# MSD.net
KiCad netlist of a schematic drawn in EAGLE
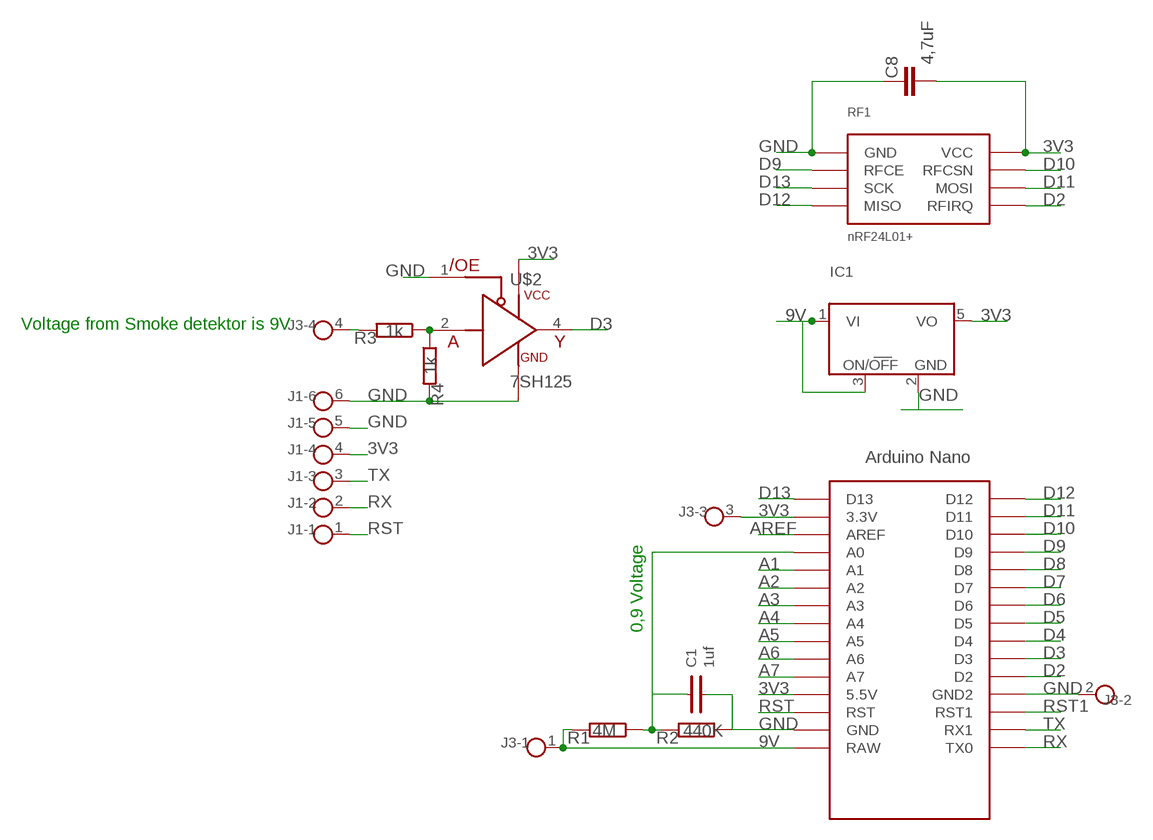
[diagram p0: schematic, sheet 1]

(export (version "E")
  (design (tool "Eeschema 10.0.6"))
  (components
    (comp (ref "C1")
      (value "1uf")
      (footprint "eagle-import:0805")
      (libsource (lib "eagle-import") (part "CC0805"))
    )
    (comp (ref "C8")
      (value "4,7uF")
      (footprint "eagle-import:C1206K")
      (libsource (lib "eagle-import") (part "C-EUC1206K"))
    )
    (comp (ref "IC1")
      (value "LP2980IM5")
      (footprint "eagle-import:SOT23-5")
      (libsource (lib "eagle-import") (part "LP2980IM5"))
    )
    (comp (ref "J1")
      (value "FTDI")
      (footprint "eagle-import:LIST6B")
      (libsource (lib "eagle-import") (part "LIST6LIST6B"))
    )
    (comp (ref "J3")
      (value "LIST4")
      (footprint "eagle-import:LIST4")
      (libsource (lib "eagle-import") (part "LIST4"))
    )
    (comp (ref "R1")
      (value "4M")
      (footprint "eagle-import:R0805")
      (libsource (lib "eagle-import") (part "R-EU_R0805"))
    )
    (comp (ref "R2")
      (value "440K")
      (footprint "eagle-import:R0805")
      (libsource (lib "eagle-import") (part "R-EU_R0805"))
    )
    (comp (ref "R3")
      (value "1k")
      (footprint "eagle-import:R0805")
      (libsource (lib "eagle-import") (part "R-EU_R0805"))
    )
    (comp (ref "R4")
      (value "1k")
      (footprint "eagle-import:R0805")
      (libsource (lib "eagle-import") (part "R-EU_R0805"))
    )
    (comp (ref "RF1")
      (value "nRF24L01+")
      (footprint "eagle-import:2X4-2.54MM")
      (libsource (lib "eagle-import") (part "NRF24L01"))
    )
    (comp (ref "U$1")
      (value "NANO")
      (footprint "eagle-import:NANO")
      (libsource (lib "eagle-import") (part "NANO"))
    )
    (comp (ref "U$2")
      (value "7SH125")
      (footprint "eagle-import:SOT23")
      (libsource (lib "eagle-import") (part "7SH125"))
    )
  )
  (nets
    (net (code "1") (name "/3V3") (class "Default")
      (node (ref "C8") (pin "1") (pinfunction "1_1") (pintype "passive"))
      (node (ref "IC1") (pin "5") (pinfunction "VO_5") (pintype "output"))
      (node (ref "J1") (pin "4") (pinfunction "1_4") (pintype "passive"))
      (node (ref "J3") (pin "3") (pinfunction "1_3") (pintype "passive"))
      (node (ref "RF1") (pin "P$2") (pinfunction "VCC_P$2") (pintype "power_in"))
      (node (ref "U$1") (pin "3.3V") (pinfunction "3.3V_3.3V") (pintype "bidirectional"))
      (node (ref "U$1") (pin "5V") (pinfunction "5.5V_5V") (pintype "bidirectional"))
      (node (ref "U$2") (pin "5") (pinfunction "VCC_5") (pintype "power_in"))
    )
    (net (code "2") (name "/9V") (class "Default")
      (node (ref "IC1") (pin "1") (pinfunction "VI_1") (pintype "input"))
      (node (ref "IC1") (pin "3") (pinfunction "ON/OFF_3") (pintype "input"))
      (node (ref "J3") (pin "1") (pinfunction "1_1") (pintype "passive"))
      (node (ref "R1") (pin "2") (pinfunction "2_2") (pintype "passive"))
      (node (ref "U$1") (pin "RAW") (pinfunction "RAW_RAW") (pintype "bidirectional"))
    )
    (net (code "3") (name "/A1") (class "Default")
      (node (ref "U$1") (pin "A1") (pinfunction "A1_A1") (pintype "bidirectional"))
    )
    (net (code "4") (name "/A2") (class "Default")
      (node (ref "U$1") (pin "A2") (pinfunction "A2_A2") (pintype "bidirectional"))
    )
    (net (code "5") (name "/A3") (class "Default")
      (node (ref "U$1") (pin "A3") (pinfunction "A3_A3") (pintype "bidirectional"))
    )
    (net (code "6") (name "/A4") (class "Default")
      (node (ref "U$1") (pin "A4") (pinfunction "A4_A4") (pintype "bidirectional"))
    )
    (net (code "7") (name "/A5") (class "Default")
      (node (ref "U$1") (pin "A5") (pinfunction "A5_A5") (pintype "bidirectional"))
    )
    (net (code "8") (name "/A6") (class "Default")
      (node (ref "U$1") (pin "A6") (pinfunction "A6_A6") (pintype "bidirectional"))
    )
    (net (code "9") (name "/A7") (class "Default")
      (node (ref "U$1") (pin "A7") (pinfunction "A7_A7") (pintype "bidirectional"))
    )
    (net (code "10") (name "/AREF") (class "Default")
      (node (ref "U$1") (pin "AREF") (pinfunction "AREF_AREF") (pintype "bidirectional"))
    )
    (net (code "11") (name "/D2") (class "Default")
      (node (ref "RF1") (pin "P$8") (pinfunction "RFIRQ_P$8") (pintype "output"))
      (node (ref "U$1") (pin "D2") (pinfunction "D2_D2") (pintype "bidirectional"))
    )
    (net (code "12") (name "/D3") (class "Default")
      (node (ref "U$1") (pin "D3") (pinfunction "D3_D3") (pintype "bidirectional"))
      (node (ref "U$2") (pin "4") (pinfunction "OUT_4") (pintype "output"))
    )
    (net (code "13") (name "/D4") (class "Default")
      (node (ref "U$1") (pin "D4") (pinfunction "D4_D4") (pintype "bidirectional"))
    )
    (net (code "14") (name "/D5") (class "Default")
      (node (ref "U$1") (pin "D5") (pinfunction "D5_D5") (pintype "bidirectional"))
    )
    (net (code "15") (name "/D6") (class "Default")
      (node (ref "U$1") (pin "D6") (pinfunction "D6_D6") (pintype "bidirectional"))
    )
    (net (code "16") (name "/D7") (class "Default")
      (node (ref "U$1") (pin "D7") (pinfunction "D7_D7") (pintype "bidirectional"))
    )
    (net (code "17") (name "/D8") (class "Default")
      (node (ref "U$1") (pin "D8") (pinfunction "D8_D8") (pintype "bidirectional"))
    )
    (net (code "18") (name "/D9") (class "Default")
      (node (ref "RF1") (pin "P$3") (pinfunction "RFCE_P$3") (pintype "input"))
      (node (ref "U$1") (pin "D9") (pinfunction "D9_D9") (pintype "bidirectional"))
    )
    (net (code "19") (name "/D10") (class "Default")
      (node (ref "RF1") (pin "P$4") (pinfunction "RFCSN_P$4") (pintype "bidirectional"))
      (node (ref "U$1") (pin "D10") (pinfunction "D10_D10") (pintype "bidirectional"))
    )
    (net (code "20") (name "/D11") (class "Default")
      (node (ref "RF1") (pin "P$6") (pinfunction "MOSI_P$6") (pintype "bidirectional"))
      (node (ref "U$1") (pin "D11") (pinfunction "D11_D11") (pintype "bidirectional"))
    )
    (net (code "21") (name "/D12") (class "Default")
      (node (ref "RF1") (pin "P$7") (pinfunction "MISO_P$7") (pintype "bidirectional"))
      (node (ref "U$1") (pin "D12") (pinfunction "D12_D12") (pintype "bidirectional"))
    )
    (net (code "22") (name "/D13") (class "Default")
      (node (ref "RF1") (pin "P$5") (pinfunction "SCK_P$5") (pintype "input"))
      (node (ref "U$1") (pin "D13") (pinfunction "D13_D13") (pintype "bidirectional"))
    )
    (net (code "23") (name "/GND") (class "Default")
      (node (ref "C1") (pin "2") (pinfunction "2_2") (pintype "passive"))
      (node (ref "C8") (pin "2") (pinfunction "2_2") (pintype "passive"))
      (node (ref "IC1") (pin "2") (pinfunction "GND_2") (pintype "power_in"))
      (node (ref "J1") (pin "5") (pinfunction "1_5") (pintype "passive"))
      (node (ref "J1") (pin "6") (pinfunction "1_6") (pintype "passive"))
      (node (ref "J3") (pin "2") (pinfunction "1_2") (pintype "passive"))
      (node (ref "R2") (pin "1") (pinfunction "1_1") (pintype "passive"))
      (node (ref "R4") (pin "2") (pinfunction "2_2") (pintype "passive"))
      (node (ref "RF1") (pin "P$1") (pinfunction "GND_P$1") (pintype "power_in"))
      (node (ref "U$1") (pin "GND") (pinfunction "GND_GND") (pintype "bidirectional"))
      (node (ref "U$1") (pin "GND1") (pinfunction "GND2_GND1") (pintype "bidirectional"))
      (node (ref "U$2") (pin "1") (pinfunction "/OE_1") (pintype "input"))
      (node (ref "U$2") (pin "3") (pinfunction "GND_3") (pintype "power_in"))
    )
    (net (code "24") (name "/RST") (class "Default")
      (node (ref "J1") (pin "1") (pinfunction "1_1") (pintype "passive"))
      (node (ref "U$1") (pin "RST") (pinfunction "RST_RST") (pintype "bidirectional"))
    )
    (net (code "25") (name "/RST1") (class "Default")
      (node (ref "U$1") (pin "RST1") (pinfunction "RST1_RST1") (pintype "bidirectional"))
    )
    (net (code "26") (name "/RX") (class "Default")
      (node (ref "J1") (pin "2") (pinfunction "1_2") (pintype "passive"))
      (node (ref "U$1") (pin "TX0") (pinfunction "TX0_TX0") (pintype "bidirectional"))
    )
    (net (code "27") (name "/TX") (class "Default")
      (node (ref "J1") (pin "3") (pinfunction "1_3") (pintype "passive"))
      (node (ref "U$1") (pin "RX1") (pinfunction "RX1_RX1") (pintype "bidirectional"))
    )
    (net (code "28") (name "Net-(C1-Pad1)") (class "Default")
      (node (ref "C1") (pin "1") (pinfunction "1_1") (pintype "passive"))
      (node (ref "R1") (pin "1") (pinfunction "1_1") (pintype "passive"))
      (node (ref "R2") (pin "2") (pinfunction "2_2") (pintype "passive"))
      (node (ref "U$1") (pin "A0") (pinfunction "A0_A0") (pintype "bidirectional"))
    )
    (net (code "29") (name "Net-(J3D-1)") (class "Default")
      (node (ref "J3") (pin "4") (pinfunction "1_4") (pintype "passive"))
      (node (ref "R3") (pin "2") (pinfunction "2_2") (pintype "passive"))
    )
    (net (code "30") (name "Net-(U$2-A)") (class "Default")
      (node (ref "R3") (pin "1") (pinfunction "1_1") (pintype "passive"))
      (node (ref "R4") (pin "1") (pinfunction "1_1") (pintype "passive"))
      (node (ref "U$2") (pin "2") (pinfunction "A_2") (pintype "input"))
    )
    (net (code "31") (name "unconnected-(U$1-PadICSP1)") (class "Default")
      (node (ref "U$1") (pin "ICSP1") (pinfunction "ICSP1_ICSP1") (pintype "bidirectional"))
    )
    (net (code "32") (name "unconnected-(U$1-PadICSP2)") (class "Default")
      (node (ref "U$1") (pin "ICSP2") (pinfunction "ICSP2_ICSP2") (pintype "bidirectional"))
    )
    (net (code "33") (name "unconnected-(U$1-PadICSP3)") (class "Default")
      (node (ref "U$1") (pin "ICSP3") (pinfunction "ICSP3_ICSP3") (pintype "bidirectional"))
    )
    (net (code "34") (name "unconnected-(U$1-PadICSP4)") (class "Default")
      (node (ref "U$1") (pin "ICSP4") (pinfunction "ICSP4_ICSP4") (pintype "bidirectional"))
    )
    (net (code "35") (name "unconnected-(U$1-PadICSP5)") (class "Default")
      (node (ref "U$1") (pin "ICSP5") (pinfunction "ICSP5_ICSP5") (pintype "bidirectional"))
    )
    (net (code "36") (name "unconnected-(U$1-PadICSP6)") (class "Default")
      (node (ref "U$1") (pin "ICSP6") (pinfunction "ICSP6_ICSP6") (pintype "bidirectional"))
    )
  )
)
